# Sheet1.net
KiCad netlist of a schematic drawn in Altium Designer
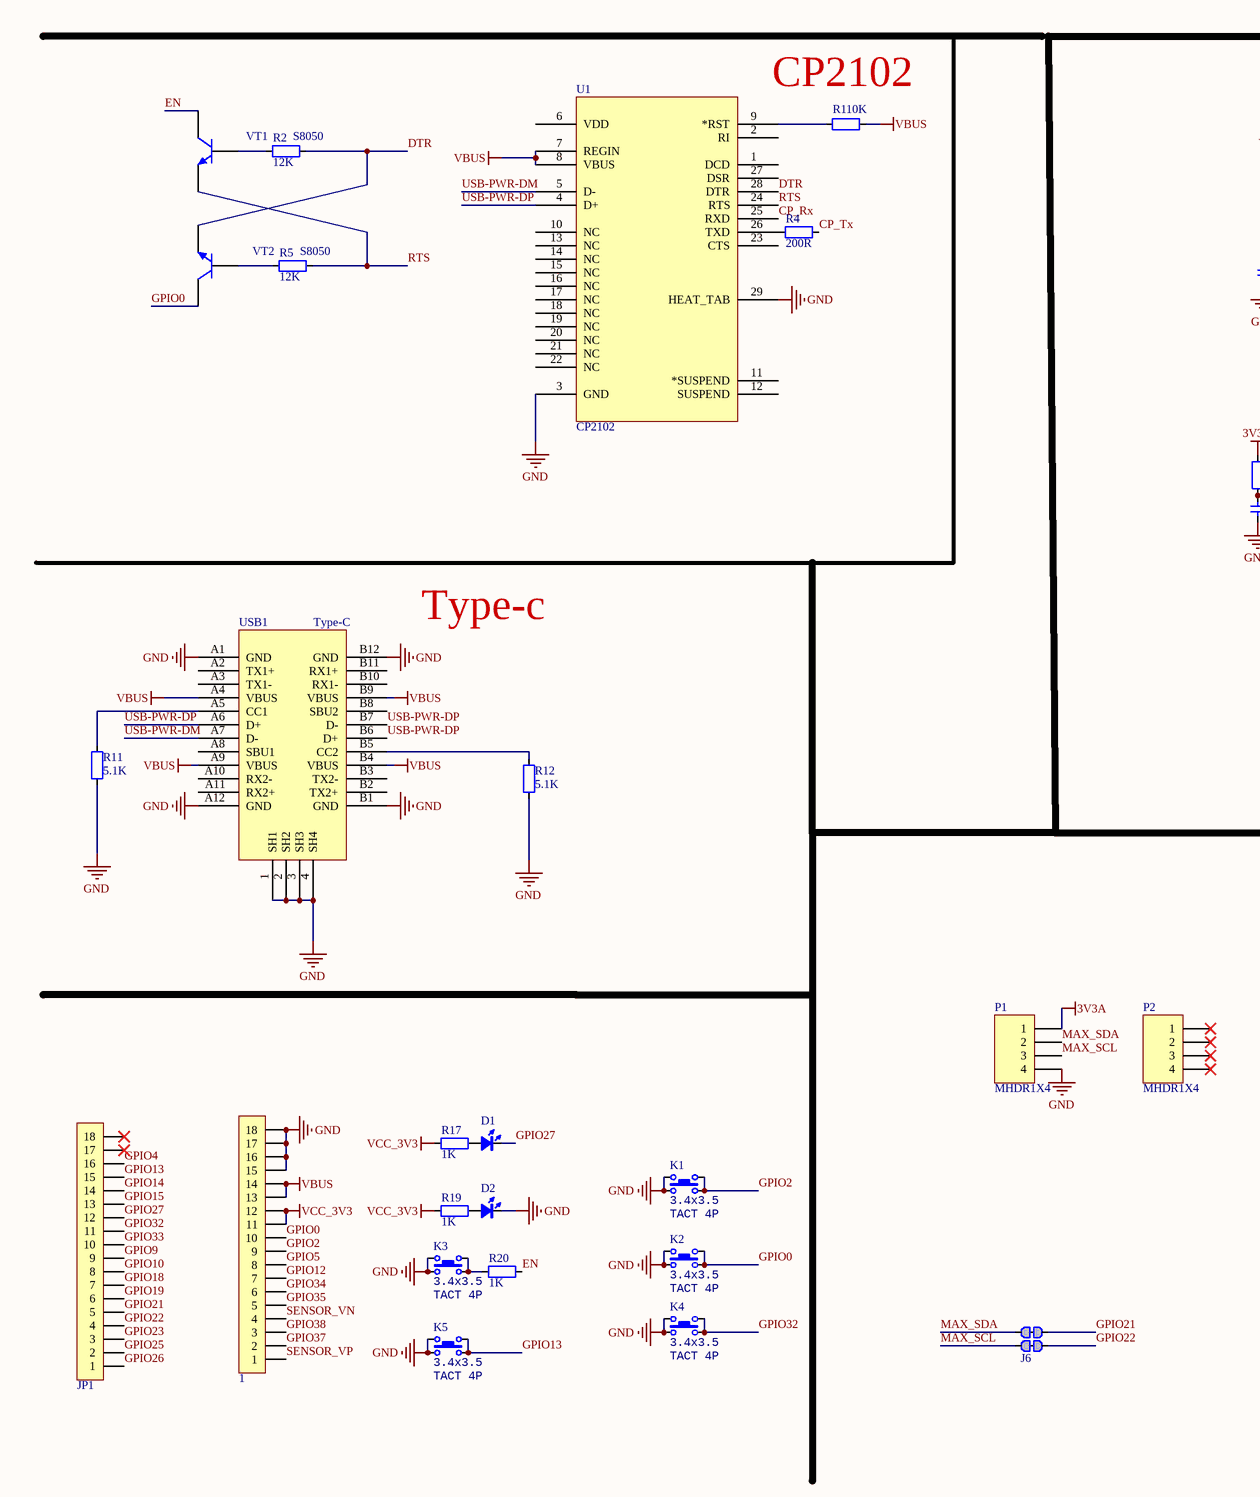
[diagram p0: Sheet1.SchDoc, left]
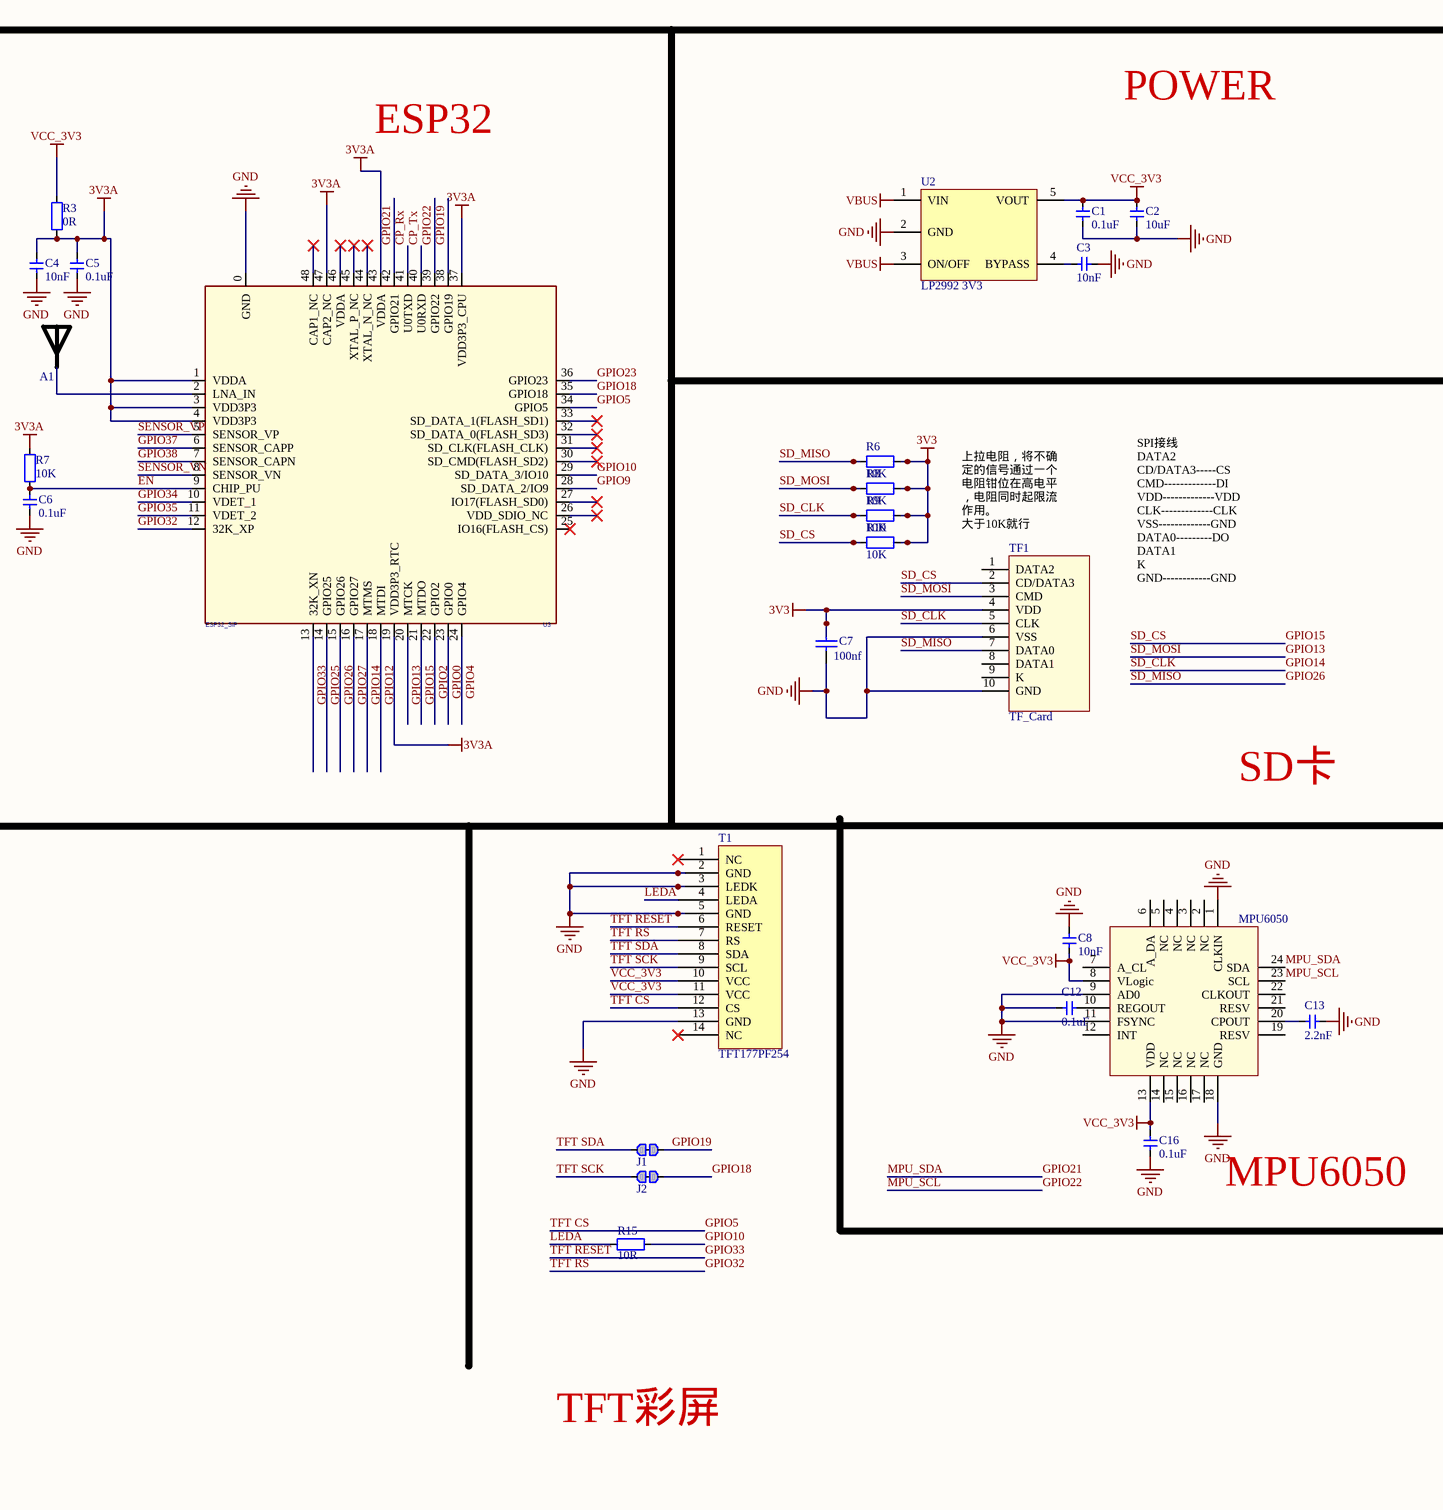
[diagram p1: Sheet1.SchDoc, right]

(export (version "E")
  (design (tool "Eeschema 10.0.6"))
  (components
    (comp (ref "1")
      (value "HDR-1X18")
      (footprint "HDR2.54-LI-18P")
      (description "18P接插件")
      (libsource (lib "5.4 - 接插件-脚距2.54 (100mil) ") (part "Header 18"))
    )
    (comp (ref "A1")
      (value "RAINSUN")
      (footprint "ANT-Rainsun-AN5120")
      (libsource (lib "ESP32-PicoDK") (part "ANT-Rainsun-AP5120"))
    )
    (comp (ref "C1")
      (value "0.1uF")
      (footprint "CAP_0402")
      (description "Capacitor")
      (libsource (lib "MyPcbLib") (part "电容-0402"))
    )
    (comp (ref "C2")
      (value "10uF")
      (footprint "CAP_0402")
      (description "Capacitor")
      (libsource (lib "MyPcbLib") (part "电容-0402"))
    )
    (comp (ref "C3")
      (value "10nF")
      (footprint "CAP_0402")
      (description "Capacitor")
      (libsource (lib "MyPcbLib") (part "电容-0402"))
    )
    (comp (ref "C4")
      (value "10nF")
      (footprint "CAP_0402")
      (description "Capacitor")
      (libsource (lib "ESP32-PicoDK") (part "电容-0402_2"))
    )
    (comp (ref "C5")
      (value "0.1uF")
      (footprint "CAP_0402")
      (description "Capacitor")
      (libsource (lib "ESP32-PicoDK") (part "电容-0402_1"))
    )
    (comp (ref "C6")
      (value "0.1uF")
      (footprint "CAP_0402")
      (description "Capacitor")
      (libsource (lib "ESP32-PicoDK") (part "电容-0402_1"))
    )
    (comp (ref "C7")
      (value "100nf")
      (footprint "CAP_0402")
      (description "Capacitor")
      (libsource (lib "0.1 - 电阻-电容-电感-电位器") (part "C"))
    )
    (comp (ref "C8")
      (value "10nF")
      (footprint "CAP_0402")
      (description "Capacitor")
      (libsource (lib "MyPcbLib") (part "电容-0402"))
    )
    (comp (ref "C12")
      (value "0.1uF")
      (footprint "CAP_0402")
      (description "Capacitor")
      (libsource (lib "MyPcbLib") (part "电容-0402"))
    )
    (comp (ref "C13")
      (value "2.2nF")
      (footprint "CAP_0402")
      (description "Capacitor")
      (libsource (lib "MyPcbLib") (part "电容-0402"))
    )
    (comp (ref "C16")
      (value "0.1uF")
      (footprint "CAP_0402")
      (description "Capacitor")
      (libsource (lib "MyPcbLib") (part "电容-0402"))
    )
    (comp (ref "D1")
      (value "color?")
      (footprint "LED_0402_RED")
      (description "LED")
      (libsource (lib "KitSprout") (part "LED_0402"))
    )
    (comp (ref "D2")
      (value "color?")
      (footprint "LED_0402_RED")
      (description "LED")
      (libsource (lib "KitSprout") (part "LED_0402"))
    )
    (comp (ref "J1")
      (value "跳线")
      (footprint "0402-0R")
      (description "Resistor")
      (fields (field (name "PUBLISHER") "Altium Limited"))
      (libsource (lib "ESP32-PicoDK") (part "跳线"))
    )
    (comp (ref "J2")
      (value "跳线")
      (footprint "0402-0R")
      (description "Resistor")
      (fields (field (name "PUBLISHER") "Altium Limited"))
      (libsource (lib "ESP32-PicoDK") (part "跳线"))
    )
    (comp (ref "J5")
      (value "跳线")
      (footprint "0402-0R")
      (description "Resistor")
      (fields (field (name "PUBLISHER") "Altium Limited"))
      (libsource (lib "ESP32-PicoDK") (part "跳线"))
    )
    (comp (ref "J6")
      (value "跳线")
      (footprint "0402-0R")
      (description "Resistor")
      (fields (field (name "PUBLISHER") "Altium Limited"))
      (libsource (lib "ESP32-PicoDK") (part "跳线"))
    )
    (comp (ref "JP1")
      (value "HDR-1X18")
      (footprint "HDR2.54-LI-18P")
      (description "18P接插件")
      (libsource (lib "5.4 - 接插件-脚距2.54 (100mil) ") (part "Header 18"))
    )
    (comp (ref "K1")
      (value "3.4x3.5")
      (footprint "ButtonTACT_3.5*3.55_90")
      (description "Button")
      (fields (field (name "TYPE") "TACT 4P") (field (name "Comment") "TACT 4P"))
      (libsource (lib "KitSprout") (part "ButtonTACT"))
    )
    (comp (ref "K2")
      (value "3.4x3.5")
      (footprint "ButtonTACT_3.5*3.55_90")
      (description "Button")
      (fields (field (name "TYPE") "TACT 4P") (field (name "Comment") "TACT 4P"))
      (libsource (lib "KitSprout") (part "ButtonTACT"))
    )
    (comp (ref "K3")
      (value "3.4x3.5")
      (footprint "SW-SMD_4P-L4.2-W3.3-P2.15-LS5.1 - duplicate")
      (description "Button")
      (fields (field (name "TYPE") "TACT 4P") (field (name "Comment") "TACT 4P"))
      (libsource (lib "KitSprout") (part "ButtonTACT"))
    )
    (comp (ref "K4")
      (value "3.4x3.5")
      (footprint "ButtonTACT_3.5*3.55_90")
      (description "Button")
      (fields (field (name "TYPE") "TACT 4P") (field (name "Comment") "TACT 4P"))
      (libsource (lib "KitSprout") (part "ButtonTACT"))
    )
    (comp (ref "K5")
      (value "3.4x3.5")
      (footprint "SW-SMD_4P-L4.2-W3.3-P2.15-LS5.1 - duplicate")
      (description "Button")
      (fields (field (name "TYPE") "TACT 4P") (field (name "Comment") "TACT 4P"))
      (libsource (lib "KitSprout") (part "ButtonTACT"))
    )
    (comp (ref "P1")
      (value "MHDR1X4")
      (footprint "金手指4")
      (description "Header, 4-Pin")
      (fields (field (name "PUBLISHER") "Altium Limited"))
      (libsource (lib "Miscellaneous Connectors") (part "MHDR1X4"))
    )
    (comp (ref "P2")
      (value "MHDR1X4")
      (footprint "金手指4")
      (description "Header, 4-Pin")
      (fields (field (name "PUBLISHER") "Altium Limited"))
      (libsource (lib "Miscellaneous Connectors") (part "MHDR1X4"))
    )
    (comp (ref "R1")
      (value "10K")
      (footprint "R0402_L")
      (description "Resistor")
      (libsource (lib "") (part "电阻-0402_1_1"))
    )
    (comp (ref "R2")
      (value "12K")
      (footprint "R0402_L")
      (description "Resistor")
      (libsource (lib "ESP32-PicoDK") (part "电阻-0402"))
    )
    (comp (ref "R3")
      (value "0R")
      (footprint "R0402_L")
      (description "Resistor")
      (libsource (lib "ESP32-PicoDK") (part "电阻-0402_3"))
    )
    (comp (ref "R4")
      (value "200R")
      (footprint "R0402_L")
      (description "Resistor")
      (libsource (lib "ESP32-PicoDK") (part "电阻-0402_2"))
    )
    (comp (ref "R5")
      (value "12K")
      (footprint "R0402_L")
      (description "Resistor")
      (libsource (lib "ESP32-PicoDK") (part "电阻-0402"))
    )
    (comp (ref "R6")
      (value "10K")
      (footprint "R0402_L")
      (description "贴片电阻")
      (libsource (lib "0.1 - 电阻-电容-电感-电位器") (part "R"))
    )
    (comp (ref "R7")
      (value "10K")
      (footprint "R0402_L")
      (description "Resistor")
      (libsource (lib "ESP32-PicoDK") (part "电阻-0402_1"))
    )
    (comp (ref "R8")
      (value "10K")
      (footprint "R0402_L")
      (description "贴片电阻")
      (libsource (lib "0.1 - 电阻-电容-电感-电位器") (part "R"))
    )
    (comp (ref "R9")
      (value "10K")
      (footprint "R0402_L")
      (description "贴片电阻")
      (libsource (lib "0.1 - 电阻-电容-电感-电位器") (part "R"))
    )
    (comp (ref "R10")
      (value "10K")
      (footprint "R0402_L")
      (description "贴片电阻")
      (libsource (lib "0.1 - 电阻-电容-电感-电位器") (part "R"))
    )
    (comp (ref "R11")
      (value "5.1K")
      (footprint "R0402_L")
      (description "Resistor")
      (libsource (lib "ESP32-PicoDK") (part "电阻-0402_7"))
    )
    (comp (ref "R12")
      (value "5.1K")
      (footprint "R0402_L")
      (description "Resistor")
      (libsource (lib "ESP32-PicoDK") (part "电阻-0402_7"))
    )
    (comp (ref "R15")
      (value "10R")
      (footprint "R0402_L")
      (description "Resistor")
      (libsource (lib "ESP32-PicoDK") (part "电阻-0402_9"))
    )
    (comp (ref "R17")
      (value "1K")
      (footprint "R0402_L")
      (description "Resistor")
      (libsource (lib "MyPcbLib") (part "电阻-0402"))
    )
    (comp (ref "R19")
      (value "1K")
      (footprint "R0402_L")
      (description "Resistor")
      (libsource (lib "MyPcbLib") (part "电阻-0402"))
    )
    (comp (ref "R20")
      (value "1K")
      (footprint "R0402_L")
      (description "Resistor")
      (libsource (lib "MyPcbLib") (part "电阻-0402"))
    )
    (comp (ref "T1")
      (value "TFT177PF254")
      (footprint "TFT144PF254")
      (libsource (lib "ESP32-PicoDK") (part "TFT177PF254"))
    )
    (comp (ref "TF1")
      (value "TF_Card")
      (footprint "Micro SD")
      (description "TF卡座")
      (libsource (lib "0.8 - 以太网-音频-Type-C USB插座") (part "TF_Card"))
    )
    (comp (ref "U1")
      (value "CP2102")
      (footprint "QFN-28")
      (description "USB转TTL")
      (libsource (lib "ESP32-PicoDK") (part "CP2102"))
    )
    (comp (ref "U2")
      (value "LP2992 3V3")
      (footprint "SOT23-5")
      (description "LDO")
      (libsource (lib "MyPcbLib") (part "LP2992"))
    )
    (comp (ref "U3")
      (value "ESP32_SIP")
      (footprint "QFN-48_7X7")
      (libsource (lib "ESP32-PicoDK") (part "ESP32-PICO"))
    )
    (comp (ref "U4")
      (value "MPU6050")
      (footprint "QFN-24")
      (description "六轴传感器")
      (libsource (lib "mLib") (part "MPU6050"))
    )
    (comp (ref "USB1")
      (value "Type-C")
      (footprint "Type-C-TOP")
      (libsource (lib "ESP32-PicoDK") (part "USB-Type-C-TOP"))
    )
    (comp (ref "VT1")
      (value "S8050")
      (footprint "SMT_TRIODE_NPN")
      (description "Surface mount NPN transistor, package SOT-23")
      (libsource (lib "MyPcbLib") (part "SMT_TRIODE_NPN"))
    )
    (comp (ref "VT2")
      (value "S8050")
      (footprint "SMT_TRIODE_NPN")
      (description "Surface mount NPN transistor, package SOT-23")
      (libsource (lib "ESP32-PicoDK") (part "SMT_TRIODE_NPN"))
    )
  )
  (nets
    (net (code "1") (name "/CP_Rx") (class "Default")
      (node (ref "U1") (pin "25") (pinfunction "RXD_25") (pintype "passive"))
      (node (ref "U3") (pin "41") (pinfunction "U0TXD_41") (pintype "power_in"))
    )
    (net (code "2") (name "/CP_Tx") (class "Default")
      (node (ref "R4") (pin "2") (pinfunction "2_2") (pintype "passive"))
      (node (ref "U3") (pin "40") (pinfunction "U0RXD_40") (pintype "power_in"))
    )
    (net (code "3") (name "/DTR") (class "Default")
      (node (ref "R2") (pin "2") (pinfunction "2_2") (pintype "passive"))
      (node (ref "U1") (pin "28") (pinfunction "DTR_28") (pintype "passive"))
      (node (ref "VT2") (pin "2") (pinfunction "E_2") (pintype "passive"))
    )
    (net (code "4") (name "/EN") (class "Default")
      (node (ref "C6") (pin "2") (pinfunction "2_2") (pintype "passive"))
      (node (ref "R20") (pin "2") (pinfunction "2_2") (pintype "passive"))
      (node (ref "R7") (pin "1") (pinfunction "1_1") (pintype "passive"))
      (node (ref "U3") (pin "9") (pinfunction "CHIP_PU_9") (pintype "passive"))
      (node (ref "VT1") (pin "3") (pinfunction "C_3") (pintype "passive"))
    )
    (net (code "5") (name "/GPIO0") (class "Default")
      (node (ref "1") (pin "10") (pinfunction "10_10") (pintype "passive"))
      (node (ref "K2") (pin "2") (pinfunction "2_2") (pintype "passive"))
      (node (ref "K2") (pin "4") (pinfunction "4_4") (pintype "passive"))
      (node (ref "U3") (pin "23") (pinfunction "GPIO0_23") (pintype "passive"))
      (node (ref "VT2") (pin "3") (pinfunction "C_3") (pintype "passive"))
    )
    (net (code "6") (name "/GPIO2") (class "Default")
      (node (ref "1") (pin "9") (pinfunction "9_9") (pintype "passive"))
      (node (ref "K1") (pin "2") (pinfunction "2_2") (pintype "passive"))
      (node (ref "K1") (pin "4") (pinfunction "4_4") (pintype "passive"))
      (node (ref "U3") (pin "22") (pinfunction "GPIO2_22") (pintype "passive"))
    )
    (net (code "7") (name "/GPIO4") (class "Default")
      (node (ref "JP1") (pin "16") (pinfunction "16_16") (pintype "passive"))
      (node (ref "U3") (pin "24") (pinfunction "GPIO4_24") (pintype "passive"))
    )
    (net (code "8") (name "/GPIO5") (class "Default")
      (node (ref "1") (pin "8") (pinfunction "8_8") (pintype "passive"))
      (node (ref "T1") (pin "12") (pinfunction "CS_12") (pintype "open_collector"))
      (node (ref "U3") (pin "34") (pinfunction "GPIO5_34") (pintype "passive"))
    )
    (net (code "9") (name "/GPIO9") (class "Default")
      (node (ref "JP1") (pin "9") (pinfunction "9_9") (pintype "passive"))
      (node (ref "U3") (pin "28") (pinfunction "SD_DATA_2/IO9_28") (pintype "passive"))
    )
    (net (code "10") (name "/GPIO10") (class "Default")
      (node (ref "JP1") (pin "8") (pinfunction "8_8") (pintype "passive"))
      (node (ref "R15") (pin "2") (pinfunction "2_2") (pintype "passive"))
      (node (ref "U3") (pin "29") (pinfunction "SD_DATA_3/IO10_29") (pintype "passive"))
    )
    (net (code "11") (name "/GPIO12") (class "Default")
      (node (ref "1") (pin "7") (pinfunction "7_7") (pintype "passive"))
      (node (ref "U3") (pin "18") (pinfunction "MTDI_18") (pintype "passive"))
    )
    (net (code "12") (name "/GPIO13") (class "Default")
      (node (ref "JP1") (pin "15") (pinfunction "15_15") (pintype "passive"))
      (node (ref "K5") (pin "2") (pinfunction "2_2") (pintype "passive"))
      (node (ref "K5") (pin "4") (pinfunction "4_4") (pintype "passive"))
      (node (ref "R8") (pin "1") (pinfunction "1_1") (pintype "passive"))
      (node (ref "TF1") (pin "3") (pinfunction "CMD_3") (pintype "passive"))
      (node (ref "U3") (pin "20") (pinfunction "MTCK_20") (pintype "passive"))
    )
    (net (code "13") (name "/GPIO14") (class "Default")
      (node (ref "JP1") (pin "14") (pinfunction "14_14") (pintype "passive"))
      (node (ref "R9") (pin "1") (pinfunction "1_1") (pintype "passive"))
      (node (ref "TF1") (pin "5") (pinfunction "CLK_5") (pintype "passive"))
      (node (ref "U3") (pin "17") (pinfunction "MTMS_17") (pintype "passive"))
    )
    (net (code "14") (name "/GPIO15") (class "Default")
      (node (ref "JP1") (pin "13") (pinfunction "13_13") (pintype "passive"))
      (node (ref "R10") (pin "1") (pinfunction "1_1") (pintype "passive"))
      (node (ref "TF1") (pin "2") (pinfunction "CD/DATA3_2") (pintype "passive"))
      (node (ref "U3") (pin "21") (pinfunction "MTDO_21") (pintype "passive"))
    )
    (net (code "15") (name "/GPIO18") (class "Default")
      (node (ref "J2") (pin "2") (pinfunction "2_2") (pintype "passive"))
      (node (ref "JP1") (pin "7") (pinfunction "7_7") (pintype "passive"))
      (node (ref "U3") (pin "35") (pinfunction "GPIO18_35") (pintype "passive"))
    )
    (net (code "16") (name "/GPIO19") (class "Default")
      (node (ref "J1") (pin "2") (pinfunction "2_2") (pintype "passive"))
      (node (ref "JP1") (pin "6") (pinfunction "6_6") (pintype "passive"))
      (node (ref "U3") (pin "38") (pinfunction "GPIO19_38") (pintype "passive"))
    )
    (net (code "17") (name "/GPIO21") (class "Default")
      (node (ref "J5") (pin "2") (pinfunction "2_2") (pintype "passive"))
      (node (ref "JP1") (pin "5") (pinfunction "5_5") (pintype "passive"))
      (node (ref "U3") (pin "42") (pinfunction "GPIO21_42") (pintype "passive"))
      (node (ref "U4") (pin "24") (pinfunction "SDA_24") (pintype "passive"))
    )
    (net (code "18") (name "/GPIO22") (class "Default")
      (node (ref "J6") (pin "2") (pinfunction "2_2") (pintype "passive"))
      (node (ref "JP1") (pin "4") (pinfunction "4_4") (pintype "passive"))
      (node (ref "U3") (pin "39") (pinfunction "GPIO22_39") (pintype "passive"))
      (node (ref "U4") (pin "23") (pinfunction "SCL_23") (pintype "passive"))
    )
    (net (code "19") (name "/GPIO23") (class "Default")
      (node (ref "JP1") (pin "3") (pinfunction "3_3") (pintype "passive"))
      (node (ref "U3") (pin "36") (pinfunction "GPIO23_36") (pintype "passive"))
    )
    (net (code "20") (name "/GPIO25") (class "Default")
      (node (ref "JP1") (pin "2") (pinfunction "2_2") (pintype "passive"))
      (node (ref "U3") (pin "14") (pinfunction "GPIO25_14") (pintype "passive"))
    )
    (net (code "21") (name "/GPIO26") (class "Default")
      (node (ref "JP1") (pin "1") (pinfunction "1_1") (pintype "passive"))
      (node (ref "R6") (pin "1") (pinfunction "1_1") (pintype "passive"))
      (node (ref "TF1") (pin "7") (pinfunction "DATA0_7") (pintype "passive"))
      (node (ref "U3") (pin "15") (pinfunction "GPIO26_15") (pintype "passive"))
    )
    (net (code "22") (name "/GPIO27") (class "Default")
      (node (ref "D1") (pin "2") (pinfunction "K_2") (pintype "passive"))
      (node (ref "JP1") (pin "12") (pinfunction "12_12") (pintype "passive"))
      (node (ref "U3") (pin "16") (pinfunction "GPIO27_16") (pintype "passive"))
    )
    (net (code "23") (name "/GPIO32") (class "Default")
      (node (ref "JP1") (pin "11") (pinfunction "11_11") (pintype "passive"))
      (node (ref "K4") (pin "2") (pinfunction "2_2") (pintype "passive"))
      (node (ref "K4") (pin "4") (pinfunction "4_4") (pintype "passive"))
      (node (ref "T1") (pin "7") (pinfunction "RS_7") (pintype "open_collector"))
      (node (ref "U3") (pin "12") (pinfunction "32K_XP_12") (pintype "passive"))
    )
    (net (code "24") (name "/GPIO33") (class "Default")
      (node (ref "JP1") (pin "10") (pinfunction "10_10") (pintype "passive"))
      (node (ref "T1") (pin "6") (pinfunction "RESET_6") (pintype "open_collector"))
      (node (ref "U3") (pin "13") (pinfunction "32K_XN_13") (pintype "passive"))
    )
    (net (code "25") (name "/GPIO34") (class "Default")
      (node (ref "1") (pin "6") (pinfunction "6_6") (pintype "passive"))
      (node (ref "U3") (pin "10") (pinfunction "VDET_1_10") (pintype "passive"))
    )
    (net (code "26") (name "/GPIO35") (class "Default")
      (node (ref "1") (pin "5") (pinfunction "5_5") (pintype "passive"))
      (node (ref "U3") (pin "11") (pinfunction "VDET_2_11") (pintype "passive"))
    )
    (net (code "27") (name "/GPIO37") (class "Default")
      (node (ref "1") (pin "2") (pinfunction "2_2") (pintype "passive"))
      (node (ref "U3") (pin "6") (pinfunction "SENSOR_CAPP_6") (pintype "passive"))
    )
    (net (code "28") (name "/GPIO38") (class "Default")
      (node (ref "1") (pin "3") (pinfunction "3_3") (pintype "passive"))
      (node (ref "U3") (pin "7") (pinfunction "SENSOR_CAPN_7") (pintype "passive"))
    )
    (net (code "29") (name "/LEDA") (class "Default")
      (node (ref "R15") (pin "1") (pinfunction "1_1") (pintype "passive"))
      (node (ref "T1") (pin "4") (pinfunction "LEDA_4") (pintype "open_collector"))
    )
    (net (code "30") (name "/MAX_SCL") (class "Default")
      (node (ref "J6") (pin "1") (pinfunction "1_1") (pintype "passive"))
      (node (ref "P1") (pin "3") (pinfunction "3_3") (pintype "passive"))
    )
    (net (code "31") (name "/MAX_SDA") (class "Default")
      (node (ref "J5") (pin "1") (pinfunction "1_1") (pintype "passive"))
      (node (ref "P1") (pin "2") (pinfunction "2_2") (pintype "passive"))
    )
    (net (code "32") (name "/RTS") (class "Default")
      (node (ref "R5") (pin "2") (pinfunction "2_2") (pintype "passive"))
      (node (ref "U1") (pin "24") (pinfunction "RTS_24") (pintype "passive"))
      (node (ref "VT1") (pin "2") (pinfunction "E_2") (pintype "passive"))
    )
    (net (code "33") (name "/SENSOR_VN") (class "Default")
      (node (ref "1") (pin "4") (pinfunction "4_4") (pintype "passive"))
      (node (ref "U3") (pin "8") (pinfunction "SENSOR_VN_8") (pintype "passive"))
    )
    (net (code "34") (name "/SENSOR_VP") (class "Default")
      (node (ref "1") (pin "1") (pinfunction "1_1") (pintype "passive"))
      (node (ref "U3") (pin "5") (pinfunction "SENSOR_VP_5") (pintype "passive"))
    )
    (net (code "35") (name "/TFT SCK") (class "Default")
      (node (ref "J2") (pin "1") (pinfunction "1_1") (pintype "passive"))
      (node (ref "T1") (pin "9") (pinfunction "SCL_9") (pintype "open_collector"))
    )
    (net (code "36") (name "/TFT SDA") (class "Default")
      (node (ref "J1") (pin "1") (pinfunction "1_1") (pintype "passive"))
      (node (ref "T1") (pin "8") (pinfunction "SDA_8") (pintype "open_collector"))
    )
    (net (code "37") (name "/USB-PWR-DM") (class "Default")
      (node (ref "U1") (pin "5") (pinfunction "D-_5") (pintype "passive"))
      (node (ref "USB1") (pin "A7") (pinfunction "D-_A7") (pintype "passive"))
    )
    (net (code "38") (name "/USB-PWR-DP") (class "Default")
      (node (ref "U1") (pin "4") (pinfunction "D+_4") (pintype "passive"))
      (node (ref "USB1") (pin "A6") (pinfunction "D+_A6") (pintype "passive"))
      (node (ref "USB1") (pin "B6") (pinfunction "D+_B6") (pintype "passive"))
      (node (ref "USB1") (pin "B7") (pinfunction "D-_B7") (pintype "passive"))
    )
    (net (code "39") (name "3V3") (class "Default")
      (node (ref "C7") (pin "2") (pinfunction "2_2") (pintype "passive"))
      (node (ref "R10") (pin "2") (pinfunction "2_2") (pintype "passive"))
      (node (ref "R6") (pin "2") (pinfunction "2_2") (pintype "passive"))
      (node (ref "R8") (pin "2") (pinfunction "2_2") (pintype "passive"))
      (node (ref "R9") (pin "2") (pinfunction "2_2") (pintype "passive"))
      (node (ref "TF1") (pin "4") (pinfunction "VDD_4") (pintype "passive"))
    )
    (net (code "40") (name "3V3A") (class "Default")
      (node (ref "C4") (pin "2") (pinfunction "2_2") (pintype "passive"))
      (node (ref "C5") (pin "2") (pinfunction "2_2") (pintype "passive"))
      (node (ref "P1") (pin "1") (pinfunction "1_1") (pintype "passive"))
      (node (ref "R3") (pin "1") (pinfunction "1_1") (pintype "passive"))
      (node (ref "R7") (pin "2") (pinfunction "2_2") (pintype "passive"))
      (node (ref "U3") (pin "1") (pinfunction "VDDA_1") (pintype "power_in"))
      (node (ref "U3") (pin "19") (pinfunction "VDD3P3_RTC_19") (pintype "power_in"))
      (node (ref "U3") (pin "3") (pinfunction "VDD3P3_3") (pintype "power_in"))
      (node (ref "U3") (pin "37") (pinfunction "VDD3P3_CPU_37") (pintype "power_in"))
      (node (ref "U3") (pin "4") (pinfunction "VDD3P3_4") (pintype "power_in"))
      (node (ref "U3") (pin "43") (pinfunction "VDDA_43") (pintype "power_in"))
      (node (ref "U3") (pin "47") (pinfunction "CAP2_NC_47") (pintype "passive"))
    )
    (net (code "41") (name "GND") (class "Default")
      (node (ref "1") (pin "15") (pinfunction "15_15") (pintype "passive"))
      (node (ref "1") (pin "16") (pinfunction "16_16") (pintype "passive"))
      (node (ref "1") (pin "17") (pinfunction "17_17") (pintype "passive"))
      (node (ref "1") (pin "18") (pinfunction "18_18") (pintype "passive"))
      (node (ref "C1") (pin "1") (pinfunction "1_1") (pintype "passive"))
      (node (ref "C12") (pin "2") (pinfunction "2_2") (pintype "passive"))
      (node (ref "C13") (pin "1") (pinfunction "1_1") (pintype "passive"))
      (node (ref "C16") (pin "1") (pinfunction "1_1") (pintype "passive"))
      (node (ref "C2") (pin "1") (pinfunction "1_1") (pintype "passive"))
      (node (ref "C3") (pin "1") (pinfunction "1_1") (pintype "passive"))
      (node (ref "C4") (pin "1") (pinfunction "1_1") (pintype "passive"))
      (node (ref "C5") (pin "1") (pinfunction "1_1") (pintype "passive"))
      (node (ref "C6") (pin "1") (pinfunction "1_1") (pintype "passive"))
      (node (ref "C7") (pin "1") (pinfunction "1_1") (pintype "passive"))
      (node (ref "C8") (pin "2") (pinfunction "2_2") (pintype "passive"))
      (node (ref "D2") (pin "2") (pinfunction "K_2") (pintype "passive"))
      (node (ref "K1") (pin "1") (pinfunction "1_1") (pintype "passive"))
      (node (ref "K1") (pin "3") (pinfunction "3_3") (pintype "passive"))
      (node (ref "K2") (pin "1") (pinfunction "1_1") (pintype "passive"))
      (node (ref "K2") (pin "3") (pinfunction "3_3") (pintype "passive"))
      (node (ref "K3") (pin "1") (pinfunction "1_1") (pintype "passive"))
      (node (ref "K3") (pin "3") (pinfunction "3_3") (pintype "passive"))
      (node (ref "K4") (pin "1") (pinfunction "1_1") (pintype "passive"))
      (node (ref "K4") (pin "3") (pinfunction "3_3") (pintype "passive"))
      (node (ref "K5") (pin "1") (pinfunction "1_1") (pintype "passive"))
      (node (ref "K5") (pin "3") (pinfunction "3_3") (pintype "passive"))
      (node (ref "P1") (pin "4") (pinfunction "4_4") (pintype "passive"))
      (node (ref "R11") (pin "2") (pinfunction "2_2") (pintype "passive"))
      (node (ref "R12") (pin "2") (pinfunction "2_2") (pintype "passive"))
      (node (ref "T1") (pin "13") (pinfunction "GND_13") (pintype "open_collector"))
      (node (ref "T1") (pin "2") (pinfunction "GND_2") (pintype "open_collector"))
      (node (ref "T1") (pin "3") (pinfunction "LEDK_3") (pintype "open_collector"))
      (node (ref "T1") (pin "5") (pinfunction "GND_5") (pintype "open_collector"))
      (node (ref "TF1") (pin "10") (pinfunction "GND_10") (pintype "passive"))
      (node (ref "TF1") (pin "6") (pinfunction "VSS_6") (pintype "passive"))
      (node (ref "U1") (pin "29") (pinfunction "HEAT_TAB_29") (pintype "passive"))
      (node (ref "U1") (pin "3") (pinfunction "GND_3") (pintype "passive"))
      (node (ref "U2") (pin "2") (pinfunction "GND_2") (pintype "passive"))
      (node (ref "U3") (pin "0") (pinfunction "GND_0") (pintype "power_in"))
      (node (ref "U4") (pin "1") (pinfunction "CLKIN_1") (pintype "passive"))
      (node (ref "U4") (pin "11") (pinfunction "FSYNC_11") (pintype "passive"))
      (node (ref "U4") (pin "18") (pinfunction "GND_18") (pintype "passive"))
      (node (ref "U4") (pin "9") (pinfunction "AD0_9") (pintype "passive"))
      (node (ref "USB1") (pin "1") (pinfunction "SH1_1") (pintype "passive"))
      (node (ref "USB1") (pin "2") (pinfunction "SH2_2") (pintype "passive"))
      (node (ref "USB1") (pin "3") (pinfunction "SH3_3") (pintype "passive"))
      (node (ref "USB1") (pin "4") (pinfunction "SH4_4") (pintype "passive"))
      (node (ref "USB1") (pin "A1") (pinfunction "GND_A1") (pintype "passive"))
      (node (ref "USB1") (pin "A12") (pinfunction "GND_A12") (pintype "passive"))
      (node (ref "USB1") (pin "B1") (pinfunction "GND_B1") (pintype "passive"))
      (node (ref "USB1") (pin "B12") (pinfunction "GND_B12") (pintype "passive"))
    )
    (net (code "42") (name "Net-(D1-A)") (class "Default")
      (node (ref "D1") (pin "1") (pinfunction "A_1") (pintype "passive"))
      (node (ref "R17") (pin "2") (pinfunction "2_2") (pintype "passive"))
    )
    (net (code "43") (name "Net-(D2-A)") (class "Default")
      (node (ref "D2") (pin "1") (pinfunction "A_1") (pintype "passive"))
      (node (ref "R19") (pin "2") (pinfunction "2_2") (pintype "passive"))
    )
    (net (code "44") (name "Net-(K3-Pad2)") (class "Default")
      (node (ref "K3") (pin "2") (pinfunction "2_2") (pintype "passive"))
      (node (ref "K3") (pin "4") (pinfunction "4_4") (pintype "passive"))
      (node (ref "R20") (pin "1") (pinfunction "1_1") (pintype "passive"))
    )
    (net (code "45") (name "Net-(U1-*RST)") (class "Default")
      (node (ref "R1") (pin "1") (pinfunction "1_1") (pintype "passive"))
      (node (ref "U1") (pin "9") (pinfunction "*RST_9") (pintype "passive"))
    )
    (net (code "46") (name "Net-(U1-TXD)") (class "Default")
      (node (ref "R4") (pin "1") (pinfunction "1_1") (pintype "passive"))
      (node (ref "U1") (pin "26") (pinfunction "TXD_26") (pintype "passive"))
    )
    (net (code "47") (name "Net-(U2-BYPASS)") (class "Default")
      (node (ref "C3") (pin "2") (pinfunction "2_2") (pintype "passive"))
      (node (ref "U2") (pin "4") (pinfunction "BYPASS_4") (pintype "passive"))
    )
    (net (code "48") (name "Net-(U3-LNA_IN)") (class "Default")
      (node (ref "A1") (pin "1") (pinfunction "1_1") (pintype "passive"))
      (node (ref "U3") (pin "2") (pinfunction "LNA_IN_2") (pintype "passive"))
    )
    (net (code "49") (name "Net-(U4-CPOUT)") (class "Default")
      (node (ref "C13") (pin "2") (pinfunction "2_2") (pintype "passive"))
      (node (ref "U4") (pin "20") (pinfunction "CPOUT_20") (pintype "passive"))
    )
    (net (code "50") (name "Net-(U4-REGOUT)") (class "Default")
      (node (ref "C12") (pin "1") (pinfunction "1_1") (pintype "passive"))
      (node (ref "U4") (pin "10") (pinfunction "REGOUT_10") (pintype "passive"))
    )
    (net (code "51") (name "Net-(USB1-CC1)") (class "Default")
      (node (ref "R11") (pin "1") (pinfunction "1_1") (pintype "passive"))
      (node (ref "USB1") (pin "A5") (pinfunction "CC1_A5") (pintype "passive"))
    )
    (net (code "52") (name "Net-(USB1-CC2)") (class "Default")
      (node (ref "R12") (pin "1") (pinfunction "1_1") (pintype "passive"))
      (node (ref "USB1") (pin "B5") (pinfunction "CC2_B5") (pintype "passive"))
    )
    (net (code "53") (name "Net-(VT1-B)") (class "Default")
      (node (ref "R2") (pin "1") (pinfunction "1_1") (pintype "passive"))
      (node (ref "VT1") (pin "1") (pinfunction "B_1") (pintype "passive"))
    )
    (net (code "54") (name "Net-(VT2-B)") (class "Default")
      (node (ref "R5") (pin "1") (pinfunction "1_1") (pintype "passive"))
      (node (ref "VT2") (pin "1") (pinfunction "B_1") (pintype "passive"))
    )
    (net (code "55") (name "VBUS") (class "Default")
      (node (ref "1") (pin "13") (pinfunction "13_13") (pintype "passive"))
      (node (ref "1") (pin "14") (pinfunction "14_14") (pintype "passive"))
      (node (ref "R1") (pin "2") (pinfunction "2_2") (pintype "passive"))
      (node (ref "U1") (pin "7") (pinfunction "REGIN_7") (pintype "passive"))
      (node (ref "U1") (pin "8") (pinfunction "VBUS_8") (pintype "passive"))
      (node (ref "U2") (pin "1") (pinfunction "VIN_1") (pintype "passive"))
      (node (ref "U2") (pin "3") (pinfunction "ON/OFF_3") (pintype "passive"))
      (node (ref "USB1") (pin "A4") (pinfunction "VBUS_A4") (pintype "passive"))
      (node (ref "USB1") (pin "A9") (pinfunction "VBUS_A9") (pintype "passive"))
      (node (ref "USB1") (pin "B4") (pinfunction "VBUS_B4") (pintype "passive"))
      (node (ref "USB1") (pin "B9") (pinfunction "VBUS_B9") (pintype "passive"))
    )
    (net (code "56") (name "VCC_3V3") (class "Default")
      (node (ref "1") (pin "11") (pinfunction "11_11") (pintype "passive"))
      (node (ref "1") (pin "12") (pinfunction "12_12") (pintype "passive"))
      (node (ref "C1") (pin "2") (pinfunction "2_2") (pintype "passive"))
      (node (ref "C16") (pin "2") (pinfunction "2_2") (pintype "passive"))
      (node (ref "C2") (pin "2") (pinfunction "2_2") (pintype "passive"))
      (node (ref "C8") (pin "1") (pinfunction "1_1") (pintype "passive"))
      (node (ref "R17") (pin "1") (pinfunction "1_1") (pintype "passive"))
      (node (ref "R19") (pin "1") (pinfunction "1_1") (pintype "passive"))
      (node (ref "R3") (pin "2") (pinfunction "2_2") (pintype "passive"))
      (node (ref "T1") (pin "10") (pinfunction "VCC_10") (pintype "open_collector"))
      (node (ref "T1") (pin "11") (pinfunction "VCC_11") (pintype "open_collector"))
      (node (ref "U2") (pin "5") (pinfunction "VOUT_5") (pintype "passive"))
      (node (ref "U4") (pin "13") (pinfunction "VDD_13") (pintype "passive"))
      (node (ref "U4") (pin "8") (pinfunction "VLogic_8") (pintype "passive"))
    )
    (net (code "57") (name "unconnected-(JP1-Pad17)") (class "Default")
      (node (ref "JP1") (pin "17") (pinfunction "17_17") (pintype "passive+no_connect"))
    )
    (net (code "58") (name "unconnected-(JP1-Pad18)") (class "Default")
      (node (ref "JP1") (pin "18") (pinfunction "18_18") (pintype "passive+no_connect"))
    )
    (net (code "59") (name "unconnected-(P2-Pad1)") (class "Default")
      (node (ref "P2") (pin "1") (pinfunction "1_1") (pintype "passive+no_connect"))
    )
    (net (code "60") (name "unconnected-(P2-Pad2)") (class "Default")
      (node (ref "P2") (pin "2") (pinfunction "2_2") (pintype "passive+no_connect"))
    )
    (net (code "61") (name "unconnected-(P2-Pad3)") (class "Default")
      (node (ref "P2") (pin "3") (pinfunction "3_3") (pintype "passive+no_connect"))
    )
    (net (code "62") (name "unconnected-(P2-Pad4)") (class "Default")
      (node (ref "P2") (pin "4") (pinfunction "4_4") (pintype "passive+no_connect"))
    )
    (net (code "63") (name "unconnected-(T1-NC-Pad1)") (class "Default")
      (node (ref "T1") (pin "1") (pinfunction "NC_1") (pintype "open_collector+no_connect"))
    )
    (net (code "64") (name "unconnected-(T1-NC-Pad14)") (class "Default")
      (node (ref "T1") (pin "14") (pinfunction "NC_14") (pintype "open_collector+no_connect"))
    )
    (net (code "65") (name "unconnected-(TF1-DATA1-Pad8)") (class "Default")
      (node (ref "TF1") (pin "8") (pinfunction "DATA1_8") (pintype "passive"))
    )
    (net (code "66") (name "unconnected-(TF1-DATA2-Pad1)") (class "Default")
      (node (ref "TF1") (pin "1") (pinfunction "DATA2_1") (pintype "passive"))
    )
    (net (code "67") (name "unconnected-(TF1-K-Pad9)") (class "Default")
      (node (ref "TF1") (pin "9") (pinfunction "K_9") (pintype "passive"))
    )
    (net (code "68") (name "unconnected-(U1-*SUSPEND-Pad11)") (class "Default")
      (node (ref "U1") (pin "11") (pinfunction "*SUSPEND_11") (pintype "passive"))
    )
    (net (code "69") (name "unconnected-(U1-CTS-Pad23)") (class "Default")
      (node (ref "U1") (pin "23") (pinfunction "CTS_23") (pintype "passive"))
    )
    (net (code "70") (name "unconnected-(U1-DCD-Pad1)") (class "Default")
      (node (ref "U1") (pin "1") (pinfunction "DCD_1") (pintype "passive"))
    )
    (net (code "71") (name "unconnected-(U1-DSR-Pad27)") (class "Default")
      (node (ref "U1") (pin "27") (pinfunction "DSR_27") (pintype "passive"))
    )
    (net (code "72") (name "unconnected-(U1-NC-Pad10)") (class "Default")
      (node (ref "U1") (pin "10") (pinfunction "NC_10") (pintype "passive"))
    )
    (net (code "73") (name "unconnected-(U1-NC-Pad13)") (class "Default")
      (node (ref "U1") (pin "13") (pinfunction "NC_13") (pintype "passive"))
    )
    (net (code "74") (name "unconnected-(U1-NC-Pad14)") (class "Default")
      (node (ref "U1") (pin "14") (pinfunction "NC_14") (pintype "passive"))
    )
    (net (code "75") (name "unconnected-(U1-NC-Pad15)") (class "Default")
      (node (ref "U1") (pin "15") (pinfunction "NC_15") (pintype "passive"))
    )
    (net (code "76") (name "unconnected-(U1-NC-Pad16)") (class "Default")
      (node (ref "U1") (pin "16") (pinfunction "NC_16") (pintype "passive"))
    )
    (net (code "77") (name "unconnected-(U1-NC-Pad17)") (class "Default")
      (node (ref "U1") (pin "17") (pinfunction "NC_17") (pintype "passive"))
    )
    (net (code "78") (name "unconnected-(U1-NC-Pad18)") (class "Default")
      (node (ref "U1") (pin "18") (pinfunction "NC_18") (pintype "passive"))
    )
    (net (code "79") (name "unconnected-(U1-NC-Pad19)") (class "Default")
      (node (ref "U1") (pin "19") (pinfunction "NC_19") (pintype "passive"))
    )
    (net (code "80") (name "unconnected-(U1-NC-Pad20)") (class "Default")
      (node (ref "U1") (pin "20") (pinfunction "NC_20") (pintype "passive"))
    )
    (net (code "81") (name "unconnected-(U1-NC-Pad21)") (class "Default")
      (node (ref "U1") (pin "21") (pinfunction "NC_21") (pintype "passive"))
    )
    (net (code "82") (name "unconnected-(U1-NC-Pad22)") (class "Default")
      (node (ref "U1") (pin "22") (pinfunction "NC_22") (pintype "passive"))
    )
    (net (code "83") (name "unconnected-(U1-RI-Pad2)") (class "Default")
      (node (ref "U1") (pin "2") (pinfunction "RI_2") (pintype "passive"))
    )
    (net (code "84") (name "unconnected-(U1-SUSPEND-Pad12)") (class "Default")
      (node (ref "U1") (pin "12") (pinfunction "SUSPEND_12") (pintype "passive"))
    )
    (net (code "85") (name "unconnected-(U1-VDD-Pad6)") (class "Default")
      (node (ref "U1") (pin "6") (pinfunction "VDD_6") (pintype "passive"))
    )
    (net (code "86") (name "unconnected-(U3-CAP1_NC-Pad48)") (class "Default")
      (node (ref "U3") (pin "48") (pinfunction "CAP1_NC_48") (pintype "passive+no_connect"))
    )
    (net (code "87") (name "unconnected-(U3-IO16(FLASH_CS)-Pad25)") (class "Default")
      (node (ref "U3") (pin "25") (pinfunction "IO16(FLASH_CS)_25") (pintype "passive+no_connect"))
    )
    (net (code "88") (name "unconnected-(U3-IO17(FLASH_SD0)-Pad27)") (class "Default")
      (node (ref "U3") (pin "27") (pinfunction "IO17(FLASH_SD0)_27") (pintype "passive+no_connect"))
    )
    (net (code "89") (name "unconnected-(U3-SD_CLK(FLASH_CLK)-Pad31)") (class "Default")
      (node (ref "U3") (pin "31") (pinfunction "SD_CLK(FLASH_CLK)_31") (pintype "passive+no_connect"))
    )
    (net (code "90") (name "unconnected-(U3-SD_CMD(FLASH_SD2)-Pad30)") (class "Default")
      (node (ref "U3") (pin "30") (pinfunction "SD_CMD(FLASH_SD2)_30") (pintype "passive+no_connect"))
    )
    (net (code "91") (name "unconnected-(U3-SD_DATA_0(FLASH_SD3)-Pad32)") (class "Default")
      (node (ref "U3") (pin "32") (pinfunction "SD_DATA_0(FLASH_SD3)_32") (pintype "passive+no_connect"))
    )
    (net (code "92") (name "unconnected-(U3-SD_DATA_1(FLASH_SD1)-Pad33)") (class "Default")
      (node (ref "U3") (pin "33") (pinfunction "SD_DATA_1(FLASH_SD1)_33") (pintype "passive+no_connect"))
    )
    (net (code "93") (name "unconnected-(U3-VDDA-Pad46)") (class "Default")
      (node (ref "U3") (pin "46") (pinfunction "VDDA_46") (pintype "power_in+no_connect"))
    )
    (net (code "94") (name "unconnected-(U3-VDD_SDIO_NC-Pad26)") (class "Default")
      (node (ref "U3") (pin "26") (pinfunction "VDD_SDIO_NC_26") (pintype "passive+no_connect"))
    )
    (net (code "95") (name "unconnected-(U3-XTAL_N_NC-Pad44)") (class "Default")
      (node (ref "U3") (pin "44") (pinfunction "XTAL_N_NC_44") (pintype "passive+no_connect"))
    )
    (net (code "96") (name "unconnected-(U3-XTAL_P_NC-Pad45)") (class "Default")
      (node (ref "U3") (pin "45") (pinfunction "XTAL_P_NC_45") (pintype "passive+no_connect"))
    )
    (net (code "97") (name "unconnected-(U4-A_CL-Pad7)") (class "Default")
      (node (ref "U4") (pin "7") (pinfunction "A_CL_7") (pintype "passive"))
    )
    (net (code "98") (name "unconnected-(U4-A_DA-Pad6)") (class "Default")
      (node (ref "U4") (pin "6") (pinfunction "A_DA_6") (pintype "passive"))
    )
    (net (code "99") (name "unconnected-(U4-CLKOUT-Pad22)") (class "Default")
      (node (ref "U4") (pin "22") (pinfunction "CLKOUT_22") (pintype "passive"))
    )
    (net (code "100") (name "unconnected-(U4-INT-Pad12)") (class "Default")
      (node (ref "U4") (pin "12") (pinfunction "INT_12") (pintype "passive"))
    )
    (net (code "101") (name "unconnected-(U4-NC-Pad2)") (class "Default")
      (node (ref "U4") (pin "2") (pinfunction "NC_2") (pintype "passive"))
    )
    (net (code "102") (name "unconnected-(U4-NC-Pad3)") (class "Default")
      (node (ref "U4") (pin "3") (pinfunction "NC_3") (pintype "passive"))
    )
    (net (code "103") (name "unconnected-(U4-NC-Pad4)") (class "Default")
      (node (ref "U4") (pin "4") (pinfunction "NC_4") (pintype "passive"))
    )
    (net (code "104") (name "unconnected-(U4-NC-Pad5)") (class "Default")
      (node (ref "U4") (pin "5") (pinfunction "NC_5") (pintype "passive"))
    )
    (net (code "105") (name "unconnected-(U4-NC-Pad14)") (class "Default")
      (node (ref "U4") (pin "14") (pinfunction "NC_14") (pintype "passive"))
    )
    (net (code "106") (name "unconnected-(U4-NC-Pad15)") (class "Default")
      (node (ref "U4") (pin "15") (pinfunction "NC_15") (pintype "passive"))
    )
    (net (code "107") (name "unconnected-(U4-NC-Pad16)") (class "Default")
      (node (ref "U4") (pin "16") (pinfunction "NC_16") (pintype "passive"))
    )
    (net (code "108") (name "unconnected-(U4-NC-Pad17)") (class "Default")
      (node (ref "U4") (pin "17") (pinfunction "NC_17") (pintype "passive"))
    )
    (net (code "109") (name "unconnected-(U4-RESV-Pad19)") (class "Default")
      (node (ref "U4") (pin "19") (pinfunction "RESV_19") (pintype "passive"))
    )
    (net (code "110") (name "unconnected-(U4-RESV-Pad21)") (class "Default")
      (node (ref "U4") (pin "21") (pinfunction "RESV_21") (pintype "passive"))
    )
    (net (code "111") (name "unconnected-(USB1-RX1+-PadB11)") (class "Default")
      (node (ref "USB1") (pin "B11") (pinfunction "RX1+_B11") (pintype "passive"))
    )
    (net (code "112") (name "unconnected-(USB1-RX1--PadB10)") (class "Default")
      (node (ref "USB1") (pin "B10") (pinfunction "RX1-_B10") (pintype "passive"))
    )
    (net (code "113") (name "unconnected-(USB1-RX2+-PadA11)") (class "Default")
      (node (ref "USB1") (pin "A11") (pinfunction "RX2+_A11") (pintype "passive"))
    )
    (net (code "114") (name "unconnected-(USB1-RX2--PadA10)") (class "Default")
      (node (ref "USB1") (pin "A10") (pinfunction "RX2-_A10") (pintype "passive"))
    )
    (net (code "115") (name "unconnected-(USB1-SBU1-PadA8)") (class "Default")
      (node (ref "USB1") (pin "A8") (pinfunction "SBU1_A8") (pintype "passive"))
    )
    (net (code "116") (name "unconnected-(USB1-SBU2-PadB8)") (class "Default")
      (node (ref "USB1") (pin "B8") (pinfunction "SBU2_B8") (pintype "passive"))
    )
    (net (code "117") (name "unconnected-(USB1-TX1+-PadA2)") (class "Default")
      (node (ref "USB1") (pin "A2") (pinfunction "TX1+_A2") (pintype "passive"))
    )
    (net (code "118") (name "unconnected-(USB1-TX1--PadA3)") (class "Default")
      (node (ref "USB1") (pin "A3") (pinfunction "TX1-_A3") (pintype "passive"))
    )
    (net (code "119") (name "unconnected-(USB1-TX2+-PadB2)") (class "Default")
      (node (ref "USB1") (pin "B2") (pinfunction "TX2+_B2") (pintype "passive"))
    )
    (net (code "120") (name "unconnected-(USB1-TX2--PadB3)") (class "Default")
      (node (ref "USB1") (pin "B3") (pinfunction "TX2-_B3") (pintype "passive"))
    )
  )
)
